# Sheet1.net
KiCad netlist of a schematic drawn in Altium Designer
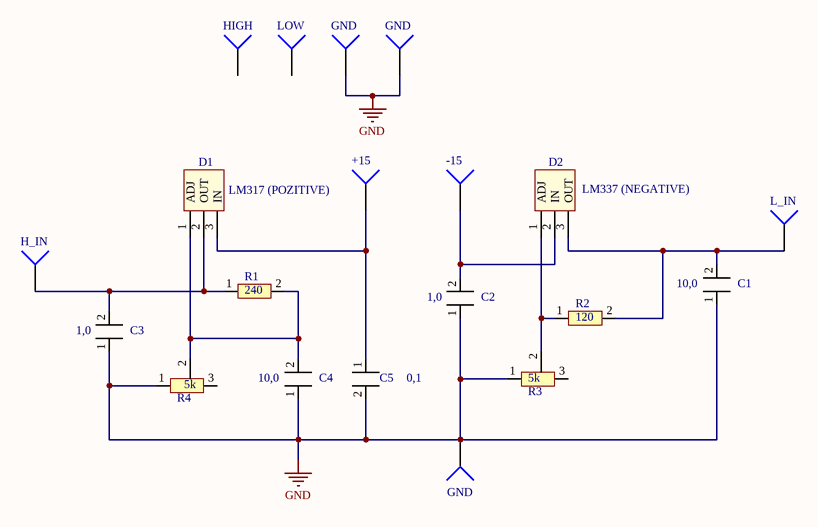
[diagram p0: Sheet1.SchDoc]

(export (version "E")
  (design (tool "Eeschema 10.0.6"))
  (components
    (comp (ref "+15")
      (value "IN")
      (footprint "PIN1")
      (description "Socket")
      (fields (field (name "PUBLISHER") "Altium Limited"))
      (libsource (lib "Miscellaneous Connectors") (part "Socket"))
    )
    (comp (ref "-15")
      (value "Socket")
      (footprint "PIN1")
      (fields (field (name "PUBLISHER") "Altium Limited"))
      (libsource (lib "Miscellaneous Connectors") (part "Socket"))
    )
    (comp (ref "C1") (value "10,0") (footprint "Cap_BIG") (libsource (lib "Schlib") (part "CAP_BIG")))
    (comp (ref "C2") (value "1,0") (footprint "CAP_SMALL") (libsource (lib "Schlib") (part "CAP_SMALL")))
    (comp (ref "C3") (value "1,0") (footprint "CAP_SMALL") (libsource (lib "Schlib") (part "CAP_SMALL")))
    (comp (ref "C4") (value "10,0") (footprint "Cap_BIG") (libsource (lib "Schlib") (part "CAP_BIG")))
    (comp (ref "C5") (value "0,1") (footprint "CAP_SMALL") (libsource (lib "Schlib") (part "CAP_SMALL")))
    (comp (ref "D1")
      (value "LM317 (POZITIVE)")
      (footprint "TO-220")
      (libsource (lib "Schlib") (part "LM317 (POZITIVE)"))
    )
    (comp (ref "D2")
      (value "LM337 (NEGATIVE)")
      (footprint "TO-220")
      (libsource (lib "Schlib") (part "LM337 (NEGATIVE)"))
    )
    (comp (ref "HIGH")
      (value "IN")
      (footprint "PIN1")
      (description "Socket")
      (fields (field (name "PUBLISHER") "Altium Limited"))
      (libsource (lib "Miscellaneous Connectors") (part "Socket"))
    )
    (comp (ref "H_IN")
      (value "IN")
      (footprint "PIN1")
      (description "Socket")
      (fields (field (name "PUBLISHER") "Altium Limited"))
      (libsource (lib "Miscellaneous Connectors") (part "Socket"))
    )
    (comp (ref "J1")
      (value "GND")
      (footprint "PIN1")
      (description "Socket")
      (fields (field (name "PUBLISHER") "Altium Limited"))
      (libsource (lib "Miscellaneous Connectors") (part "Socket"))
    )
    (comp (ref "J2")
      (value "GND")
      (footprint "PIN1")
      (description "Socket")
      (fields (field (name "PUBLISHER") "Altium Limited"))
      (libsource (lib "Miscellaneous Connectors") (part "Socket"))
    )
    (comp (ref "J3")
      (value "GND")
      (footprint "PIN1")
      (description "Socket")
      (fields (field (name "PUBLISHER") "Altium Limited"))
      (libsource (lib "Miscellaneous Connectors") (part "Socket"))
    )
    (comp (ref "LOW")
      (value "IN")
      (footprint "PIN1")
      (description "Socket")
      (fields (field (name "PUBLISHER") "Altium Limited"))
      (libsource (lib "Miscellaneous Connectors") (part "Socket"))
    )
    (comp (ref "L_IN")
      (value "IN")
      (footprint "PIN1")
      (description "Socket")
      (fields (field (name "PUBLISHER") "Altium Limited"))
      (libsource (lib "Miscellaneous Connectors") (part "Socket"))
    )
    (comp (ref "R1") (value "240") (footprint "RES") (libsource (lib "Schlib") (part "RES")))
    (comp (ref "R2") (value "120") (footprint "RES") (libsource (lib "Schlib") (part "RES")))
    (comp (ref "R3") (value "5k") (footprint "PODSR_RES") (libsource (lib "Schlib") (part "RES_PODSTR")))
    (comp (ref "R4") (value "5k") (footprint "PODSR_RES") (libsource (lib "Schlib") (part "RES_PODSTR")))
  )
  (nets
    (net (code "1") (name "GND") (class "Default")
      (node (ref "C1") (pin "1") (pinfunction "1_1") (pintype "passive"))
      (node (ref "C2") (pin "1") (pinfunction "1_1") (pintype "passive"))
      (node (ref "C3") (pin "1") (pinfunction "1_1") (pintype "passive"))
      (node (ref "C4") (pin "1") (pinfunction "1_1") (pintype "passive"))
      (node (ref "C5") (pin "2") (pinfunction "2_2") (pintype "passive"))
      (node (ref "J1") (pin "1") (pinfunction "1_1") (pintype "passive"))
      (node (ref "J2") (pin "1") (pinfunction "1_1") (pintype "passive"))
      (node (ref "J3") (pin "1") (pinfunction "1_1") (pintype "passive"))
      (node (ref "R3") (pin "1") (pinfunction "1_1") (pintype "passive"))
      (node (ref "R4") (pin "1") (pinfunction "1_1") (pintype "passive"))
    )
    (net (code "2") (name "Net-(D1-ADJ)") (class "Default")
      (node (ref "C4") (pin "2") (pinfunction "2_2") (pintype "passive"))
      (node (ref "D1") (pin "1") (pinfunction "ADJ_1") (pintype "passive"))
      (node (ref "R1") (pin "2") (pinfunction "2_2") (pintype "passive"))
      (node (ref "R4") (pin "2") (pinfunction "2_2") (pintype "passive"))
    )
    (net (code "3") (name "Net-(D1-IN)") (class "Default")
      (node (ref "+15") (pin "1") (pinfunction "1_1") (pintype "passive"))
      (node (ref "C5") (pin "1") (pinfunction "1_1") (pintype "passive"))
      (node (ref "D1") (pin "3") (pinfunction "IN_3") (pintype "passive"))
    )
    (net (code "4") (name "Net-(D1-OUT)") (class "Default")
      (node (ref "C3") (pin "2") (pinfunction "2_2") (pintype "passive"))
      (node (ref "D1") (pin "2") (pinfunction "OUT_2") (pintype "passive"))
      (node (ref "H_IN") (pin "1") (pinfunction "1_1") (pintype "passive"))
      (node (ref "R1") (pin "1") (pinfunction "1_1") (pintype "passive"))
    )
    (net (code "5") (name "Net-(D2-ADJ)") (class "Default")
      (node (ref "D2") (pin "1") (pinfunction "ADJ_1") (pintype "passive"))
      (node (ref "R2") (pin "1") (pinfunction "1_1") (pintype "passive"))
      (node (ref "R3") (pin "2") (pinfunction "2_2") (pintype "passive"))
    )
    (net (code "6") (name "Net-(D2-IN)") (class "Default")
      (node (ref "-15") (pin "1") (pinfunction "1_1") (pintype "passive"))
      (node (ref "C2") (pin "2") (pinfunction "2_2") (pintype "passive"))
      (node (ref "D2") (pin "2") (pinfunction "IN_2") (pintype "passive"))
    )
    (net (code "7") (name "Net-(D2-OUT)") (class "Default")
      (node (ref "C1") (pin "2") (pinfunction "2_2") (pintype "passive"))
      (node (ref "D2") (pin "3") (pinfunction "OUT_3") (pintype "passive"))
      (node (ref "L_IN") (pin "1") (pinfunction "1_1") (pintype "passive"))
      (node (ref "R2") (pin "2") (pinfunction "2_2") (pintype "passive"))
    )
    (net (code "8") (name "unconnected-(HIGH-Pad1)") (class "Default")
      (node (ref "HIGH") (pin "1") (pinfunction "1_1") (pintype "passive"))
    )
    (net (code "9") (name "unconnected-(LOW-Pad1)") (class "Default")
      (node (ref "LOW") (pin "1") (pinfunction "1_1") (pintype "passive"))
    )
    (net (code "10") (name "unconnected-(R3-Pad3)") (class "Default")
      (node (ref "R3") (pin "3") (pinfunction "3_3") (pintype "passive"))
    )
    (net (code "11") (name "unconnected-(R4-Pad3)") (class "Default")
      (node (ref "R4") (pin "3") (pinfunction "3_3") (pintype "passive"))
    )
  )
)
